# RGB_Identifier_for_intelligent_instructi.net
KiCad netlist of a schematic drawn in Altium Designer
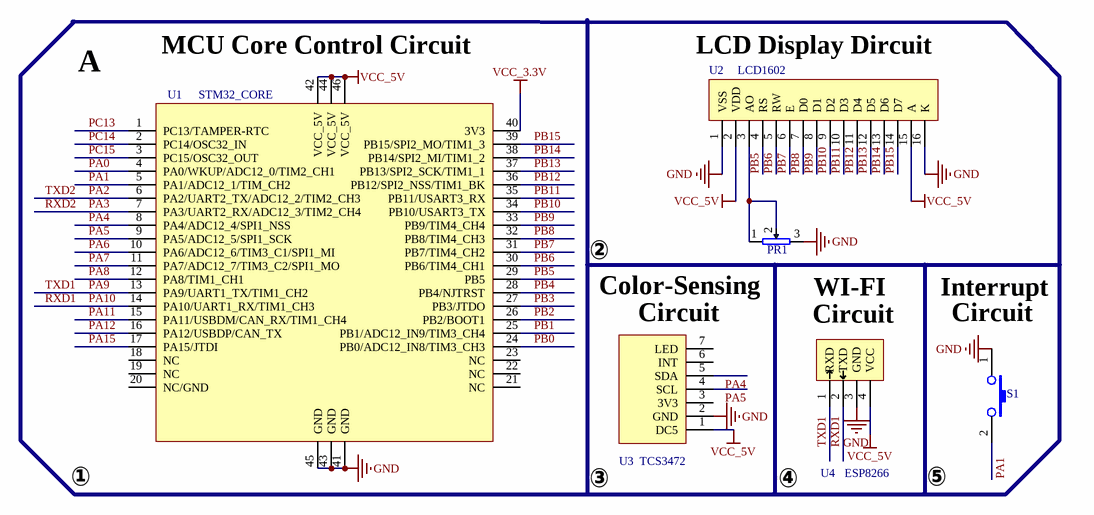
[diagram p0: RGB Identifier for intelligent instruction label.SchDoc]

(export (version "E")
  (design (tool "Eeschema 10.0.6"))
  (components
    (comp (ref "PR1")
      (value "103")
      (footprint "TWKJ_S:WH06-2")
      (description "电位器")
      (libsource (lib "TWKJ_S") (part "PR"))
    )
    (comp (ref "S1")
      (value "Button")
      (footprint "TWKJ_S:BUTTON_6x6DIP")
      (description "按键")
      (libsource (lib "TWKJ_S") (part "Button"))
    )
    (comp (ref "U1")
      (value "STM32_CORE")
      (footprint "TWKJ_S:STM32_CORE")
      (description "STM32核心板")
      (libsource (lib "TWKJ_S") (part "STM32_CORE"))
    )
    (comp (ref "U2")
      (value "LCD1602")
      (footprint "TWKJ_S:LCD1602")
      (description "LCD1602液晶")
      (libsource (lib "TWKJ_S") (part "LCD1602"))
    )
    (comp (ref "U3") (value "TCS3472") (footprint "TCS3472_MODE") (libsource (lib "TWKJ_S") (part "TCS3472")))
    (comp (ref "U4")
      (value "ESP8266")
      (footprint "TWKJ_S:蓝牙MODE竖放")
      (description "蓝牙模块")
      (libsource (lib "TWKJ_S") (part "蓝牙MODE"))
    )
  )
  (nets
    (net (code "1") (name "/PA0") (class "Default")
      (node (ref "U1") (pin "4") (pinfunction "PA0/WKUP/ADC12_0/TIM2_CH1_4") (pintype "passive"))
    )
    (net (code "2") (name "/PA1") (class "Default")
      (node (ref "S1") (pin "2") (pinfunction "2_2") (pintype "passive"))
      (node (ref "U1") (pin "5") (pinfunction "PA1/ADC12_1/TIM_CH2_5") (pintype "passive"))
    )
    (net (code "3") (name "/PA2") (class "Default")
      (node (ref "U1") (pin "6") (pinfunction "PA2/UART2_TX/ADC12_2/TIM2_CH3_6") (pintype "passive"))
    )
    (net (code "4") (name "/PA3") (class "Default")
      (node (ref "U1") (pin "7") (pinfunction "PA3/UART2_RX/ADC12_3/TIM2_CH4_7") (pintype "passive"))
    )
    (net (code "5") (name "/PA4") (class "Default")
      (node (ref "U1") (pin "8") (pinfunction "PA4/ADC12_4/SPI1_NSS_8") (pintype "passive"))
      (node (ref "U3") (pin "5") (pinfunction "SDA_5") (pintype "passive"))
    )
    (net (code "6") (name "/PA5") (class "Default")
      (node (ref "U1") (pin "9") (pinfunction "PA5/ADC12_5/SPI1_SCK_9") (pintype "passive"))
      (node (ref "U3") (pin "4") (pinfunction "SCL_4") (pintype "passive"))
    )
    (net (code "7") (name "/PA6") (class "Default")
      (node (ref "U1") (pin "10") (pinfunction "PA6/ADC12_6/TIM3_C1/SPI1_MI_10") (pintype "passive"))
    )
    (net (code "8") (name "/PA7") (class "Default")
      (node (ref "U1") (pin "11") (pinfunction "PA7/ADC12_7/TIM3_C2/SPI1_MO_11") (pintype "passive"))
    )
    (net (code "9") (name "/PA8") (class "Default")
      (node (ref "U1") (pin "12") (pinfunction "PA8/TIM1_CH1_12") (pintype "passive"))
    )
    (net (code "10") (name "/PA9") (class "Default")
      (node (ref "U1") (pin "13") (pinfunction "PA9/UART1_TX/TIM1_CH2_13") (pintype "passive"))
      (node (ref "U4") (pin "1") (pinfunction "RXD_1") (pintype "passive"))
    )
    (net (code "11") (name "/PA10") (class "Default")
      (node (ref "U1") (pin "14") (pinfunction "PA10/UART1_RX/TIM1_CH3_14") (pintype "passive"))
      (node (ref "U4") (pin "2") (pinfunction "TXD_2") (pintype "passive"))
    )
    (net (code "12") (name "/PA11") (class "Default")
      (node (ref "U1") (pin "15") (pinfunction "PA11/USBDM/CAN_RX/TIM1_CH4_15") (pintype "passive"))
    )
    (net (code "13") (name "/PA12") (class "Default")
      (node (ref "U1") (pin "16") (pinfunction "PA12/USBDP/CAN_TX_16") (pintype "passive"))
    )
    (net (code "14") (name "/PA15") (class "Default")
      (node (ref "U1") (pin "17") (pinfunction "PA15/JTDI_17") (pintype "passive"))
    )
    (net (code "15") (name "/PB0") (class "Default")
      (node (ref "U1") (pin "24") (pinfunction "PB0/ADC12_IN8/TIM3_CH3_24") (pintype "passive"))
    )
    (net (code "16") (name "/PB1") (class "Default")
      (node (ref "U1") (pin "25") (pinfunction "PB1/ADC12_IN9/TIM3_CH4_25") (pintype "passive"))
    )
    (net (code "17") (name "/PB2") (class "Default")
      (node (ref "U1") (pin "26") (pinfunction "PB2/BOOT1_26") (pintype "passive"))
    )
    (net (code "18") (name "/PB3") (class "Default")
      (node (ref "U1") (pin "27") (pinfunction "PB3/JTDO_27") (pintype "passive"))
    )
    (net (code "19") (name "/PB4") (class "Default")
      (node (ref "U1") (pin "28") (pinfunction "PB4/NJTRST_28") (pintype "passive"))
    )
    (net (code "20") (name "/PB5") (class "Default")
      (node (ref "U1") (pin "29") (pinfunction "PB5_29") (pintype "passive"))
      (node (ref "U2") (pin "4") (pinfunction "RS_4") (pintype "passive"))
    )
    (net (code "21") (name "/PB6") (class "Default")
      (node (ref "U1") (pin "30") (pinfunction "PB6/TIM4_CH1_30") (pintype "passive"))
      (node (ref "U2") (pin "5") (pinfunction "RW_5") (pintype "passive"))
    )
    (net (code "22") (name "/PB7") (class "Default")
      (node (ref "U1") (pin "31") (pinfunction "PB7/TIM4_CH2_31") (pintype "passive"))
      (node (ref "U2") (pin "6") (pinfunction "E_6") (pintype "passive"))
    )
    (net (code "23") (name "/PB8") (class "Default")
      (node (ref "U1") (pin "32") (pinfunction "PB8/TIM4_CH3_32") (pintype "passive"))
      (node (ref "U2") (pin "7") (pinfunction "D0_7") (pintype "passive"))
    )
    (net (code "24") (name "/PB9") (class "Default")
      (node (ref "U1") (pin "33") (pinfunction "PB9/TIM4_CH4_33") (pintype "passive"))
      (node (ref "U2") (pin "8") (pinfunction "D1_8") (pintype "passive"))
    )
    (net (code "25") (name "/PB10") (class "Default")
      (node (ref "U1") (pin "34") (pinfunction "PB10/USART3_TX_34") (pintype "passive"))
      (node (ref "U2") (pin "9") (pinfunction "D2_9") (pintype "passive"))
    )
    (net (code "26") (name "/PB11") (class "Default")
      (node (ref "U1") (pin "35") (pinfunction "PB11/USART3_RX_35") (pintype "passive"))
      (node (ref "U2") (pin "10") (pinfunction "D3_10") (pintype "passive"))
    )
    (net (code "27") (name "/PB12") (class "Default")
      (node (ref "U1") (pin "36") (pinfunction "PB12/SPI2_NSS/TIM1_BK_36") (pintype "passive"))
      (node (ref "U2") (pin "11") (pinfunction "D4_11") (pintype "passive"))
    )
    (net (code "28") (name "/PB13") (class "Default")
      (node (ref "U1") (pin "37") (pinfunction "PB13/SPI2_SCK/TIM1_1_37") (pintype "passive"))
      (node (ref "U2") (pin "12") (pinfunction "D5_12") (pintype "passive"))
    )
    (net (code "29") (name "/PB14") (class "Default")
      (node (ref "U1") (pin "38") (pinfunction "PB14/SPI2_MI/TIM1_2_38") (pintype "passive"))
      (node (ref "U2") (pin "13") (pinfunction "D6_13") (pintype "passive"))
    )
    (net (code "30") (name "/PB15") (class "Default")
      (node (ref "U1") (pin "39") (pinfunction "PB15/SPI2_MO/TIM1_3_39") (pintype "passive"))
      (node (ref "U2") (pin "14") (pinfunction "D7_14") (pintype "passive"))
    )
    (net (code "31") (name "/PC13") (class "Default")
      (node (ref "U1") (pin "1") (pinfunction "PC13/TAMPER-RTC_1") (pintype "passive"))
    )
    (net (code "32") (name "/PC14") (class "Default")
      (node (ref "U1") (pin "2") (pinfunction "PC14/OSC32_IN_2") (pintype "passive"))
    )
    (net (code "33") (name "/PC15") (class "Default")
      (node (ref "U1") (pin "3") (pinfunction "PC15/OSC32_OUT_3") (pintype "passive"))
    )
    (net (code "34") (name "GND") (class "Default")
      (node (ref "PR1") (pin "3") (pinfunction "3_3") (pintype "passive"))
      (node (ref "S1") (pin "1") (pinfunction "1_1") (pintype "passive"))
      (node (ref "U1") (pin "41") (pinfunction "GND_41") (pintype "passive"))
      (node (ref "U1") (pin "43") (pinfunction "GND_43") (pintype "passive"))
      (node (ref "U1") (pin "45") (pinfunction "GND_45") (pintype "passive"))
      (node (ref "U2") (pin "1") (pinfunction "VSS_1") (pintype "passive"))
      (node (ref "U2") (pin "16") (pinfunction "K_16") (pintype "passive"))
      (node (ref "U3") (pin "2") (pinfunction "GND_2") (pintype "passive"))
      (node (ref "U4") (pin "3") (pinfunction "GND_3") (pintype "passive"))
    )
    (net (code "35") (name "Net-(U2-AO)") (class "Default")
      (node (ref "PR1") (pin "1") (pinfunction "1_1") (pintype "passive"))
      (node (ref "PR1") (pin "2") (pinfunction "2_2") (pintype "passive"))
      (node (ref "U2") (pin "3") (pinfunction "AO_3") (pintype "passive"))
    )
    (net (code "36") (name "VCC_3.3V") (class "Default")
      (node (ref "U1") (pin "40") (pinfunction "3V3_40") (pintype "passive"))
    )
    (net (code "37") (name "VCC_5V") (class "Default")
      (node (ref "U1") (pin "42") (pinfunction "VCC_5V_42") (pintype "passive"))
      (node (ref "U1") (pin "44") (pinfunction "VCC_5V_44") (pintype "passive"))
      (node (ref "U1") (pin "46") (pinfunction "VCC_5V_46") (pintype "passive"))
      (node (ref "U2") (pin "15") (pinfunction "A_15") (pintype "passive"))
      (node (ref "U2") (pin "2") (pinfunction "VDD_2") (pintype "passive"))
      (node (ref "U3") (pin "1") (pinfunction "DC5_1") (pintype "passive"))
      (node (ref "U4") (pin "4") (pinfunction "VCC_4") (pintype "passive"))
    )
    (net (code "38") (name "unconnected-(U1-NC-Pad18)") (class "Default")
      (node (ref "U1") (pin "18") (pinfunction "NC_18") (pintype "passive"))
    )
    (net (code "39") (name "unconnected-(U1-NC-Pad19)") (class "Default")
      (node (ref "U1") (pin "19") (pinfunction "NC_19") (pintype "passive"))
    )
    (net (code "40") (name "unconnected-(U1-NC-Pad21)") (class "Default")
      (node (ref "U1") (pin "21") (pinfunction "NC_21") (pintype "passive"))
    )
    (net (code "41") (name "unconnected-(U1-NC-Pad22)") (class "Default")
      (node (ref "U1") (pin "22") (pinfunction "NC_22") (pintype "passive"))
    )
    (net (code "42") (name "unconnected-(U1-NC-Pad23)") (class "Default")
      (node (ref "U1") (pin "23") (pinfunction "NC_23") (pintype "passive"))
    )
    (net (code "43") (name "unconnected-(U1-NC{slash}GND-Pad20)") (class "Default")
      (node (ref "U1") (pin "20") (pinfunction "NC/GND_20") (pintype "passive"))
    )
    (net (code "44") (name "unconnected-(U3-3V3-Pad3)") (class "Default")
      (node (ref "U3") (pin "3") (pinfunction "3V3_3") (pintype "passive"))
    )
    (net (code "45") (name "unconnected-(U3-INT-Pad6)") (class "Default")
      (node (ref "U3") (pin "6") (pinfunction "INT_6") (pintype "passive"))
    )
    (net (code "46") (name "unconnected-(U3-LED-Pad7)") (class "Default")
      (node (ref "U3") (pin "7") (pinfunction "LED_7") (pintype "passive"))
    )
  )
)
